# SBH_Charger_USB_PD.net
KiCad netlist of a schematic drawn in Altium Designer
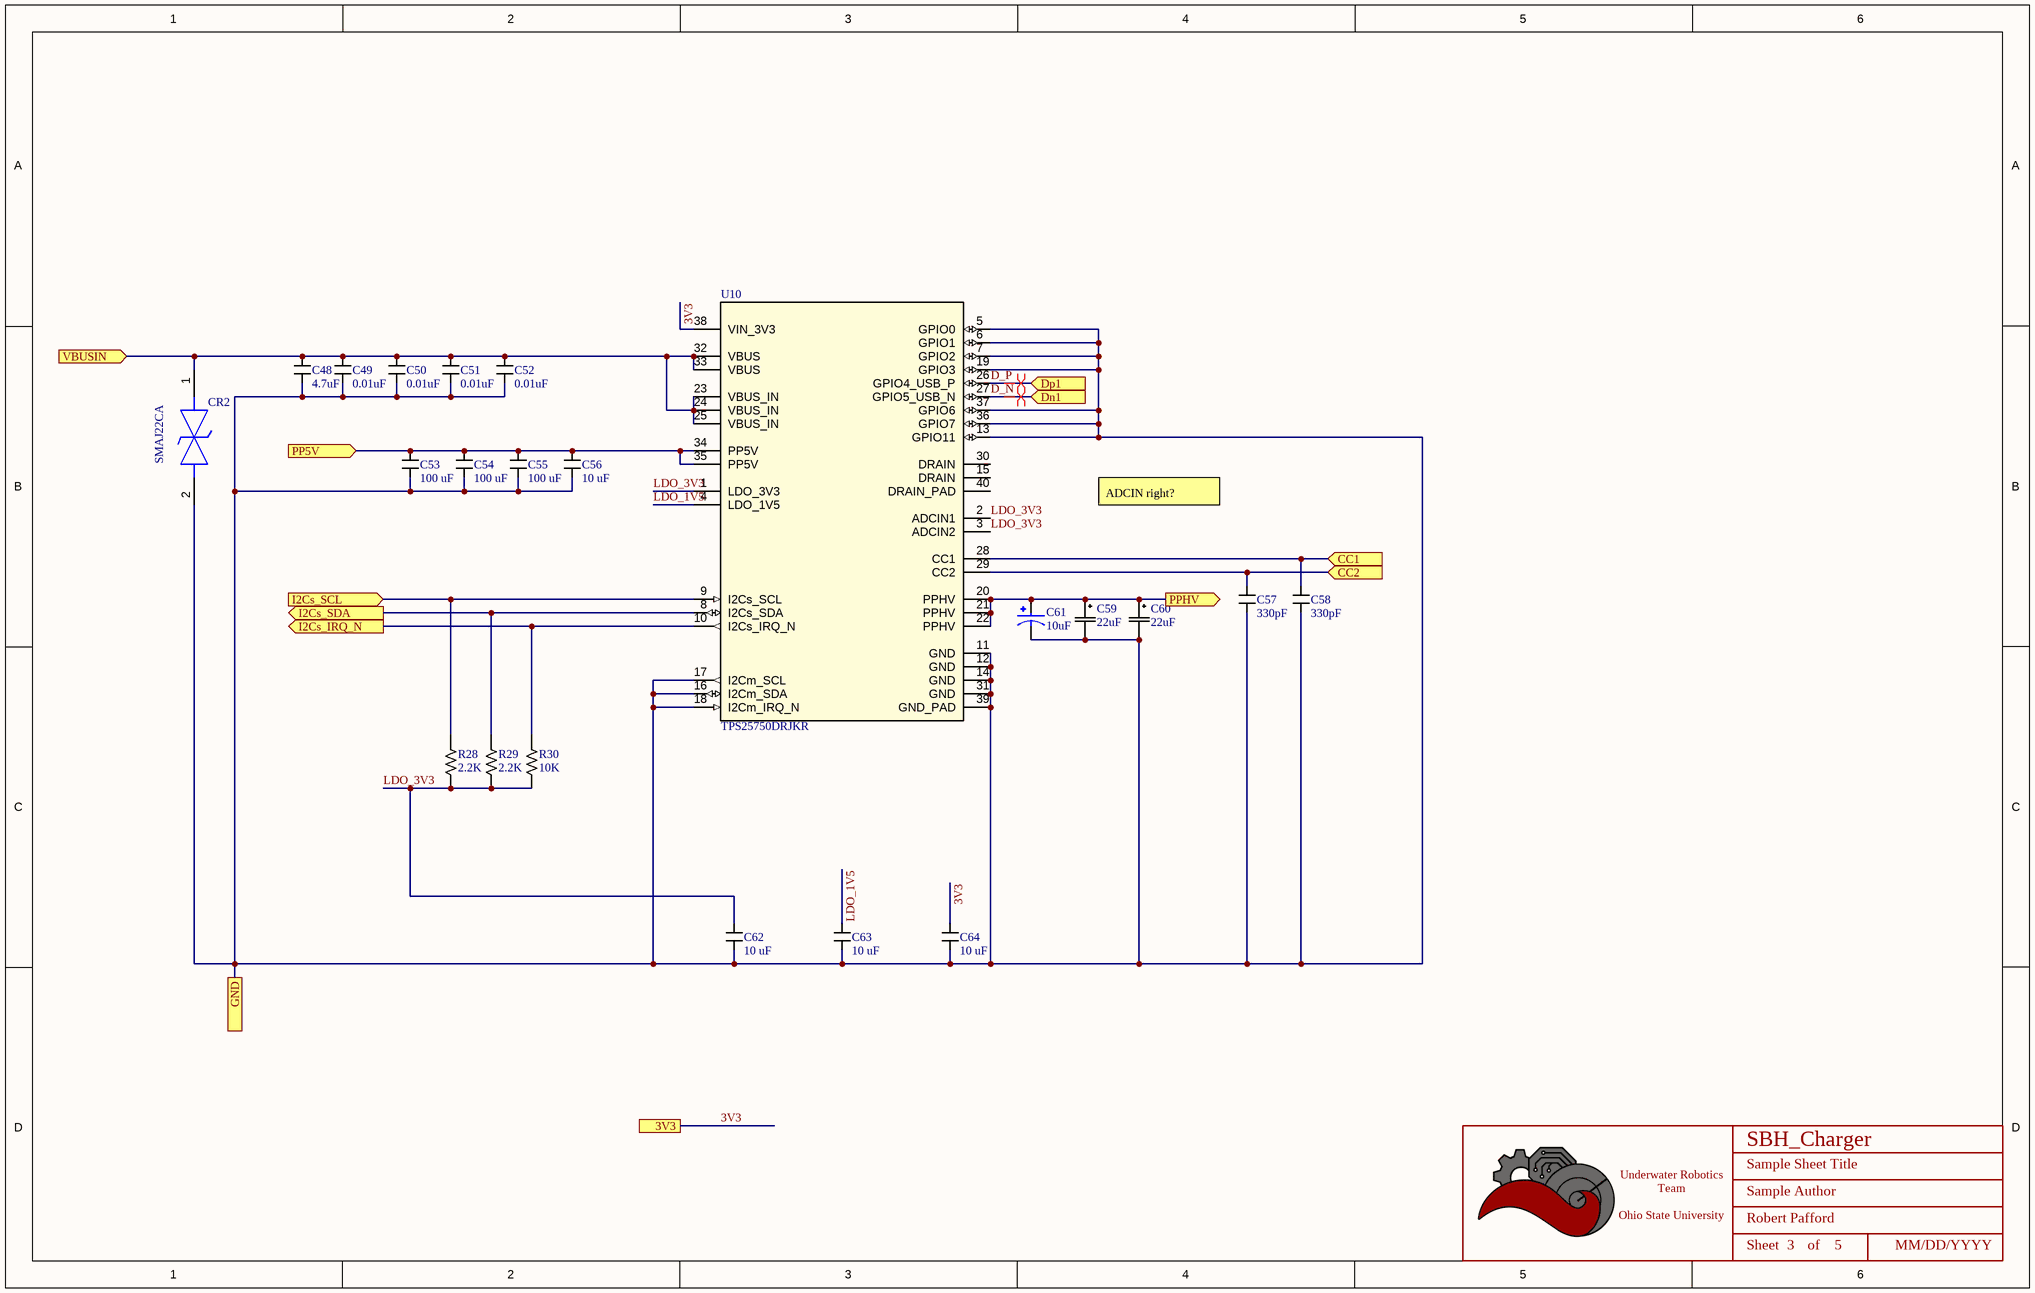
[diagram p0: SBH_Charger_USB_PD.SchDoc]

(export (version "E")
  (design (tool "Eeschema 10.0.6"))
  (components
    (comp (ref "C48")
      (value "4.7uF")
      (footprint "CAPACITOR_0603")
      (description "Cap 4.7uF 6.3V +/-10%\r\nCeramic 0603")
      (fields
        (field (name "TOLERANCE") "+/- 10%")
        (field (name "VOLTAGE") "6.3V")
        (field (name "MADE BY") "Robert Pafford")
      )
      (libsource (lib "Capacitors") (part "CAPACITOR_4.7uF_0603"))
    )
    (comp (ref "C49")
      (value "0.01uF")
      (footprint "CAPACITOR_0603")
      (description "Cap 10nF 6.3V +/-20%\r\nCeramic 0603")
      (fields
        (field (name "TOLERANCE") "+/- 10%")
        (field (name "VOLTAGE") "6.3V")
        (field (name "MADE BY") "Flip B")
      )
      (libsource (lib "Capacitors") (part "CAPACITOR_0.01uF_0603"))
    )
    (comp (ref "C50")
      (value "0.01uF")
      (footprint "CAPACITOR_0603")
      (description "Cap 10nF 6.3V +/-20%\r\nCeramic 0603")
      (fields
        (field (name "TOLERANCE") "+/- 10%")
        (field (name "VOLTAGE") "6.3V")
        (field (name "MADE BY") "Flip B")
      )
      (libsource (lib "Capacitors") (part "CAPACITOR_0.01uF_0603"))
    )
    (comp (ref "C51")
      (value "0.01uF")
      (footprint "CAPACITOR_0603")
      (description "Cap 10nF 6.3V +/-20%\r\nCeramic 0603")
      (fields
        (field (name "TOLERANCE") "+/- 10%")
        (field (name "VOLTAGE") "6.3V")
        (field (name "MADE BY") "Flip B")
      )
      (libsource (lib "Capacitors") (part "CAPACITOR_0.01uF_0603"))
    )
    (comp (ref "C52")
      (value "0.01uF")
      (footprint "CAPACITOR_0603")
      (description "Cap 10nF 6.3V +/-20%\r\nCeramic 0603")
      (fields
        (field (name "TOLERANCE") "+/- 10%")
        (field (name "VOLTAGE") "6.3V")
        (field (name "MADE BY") "Flip B")
      )
      (libsource (lib "Capacitors") (part "CAPACITOR_0.01uF_0603"))
    )
    (comp (ref "C53")
      (value "100uF Ceramic 6.3V")
      (footprint "CAPACITOR_0603")
      (description "Cap 100uF 6.3V +/-20%\r\nCeramic 0603")
      (fields
        (field (name "TOLERANCE") "+/- 20%")
        (field (name "VOLTAGE") "6.3V")
        (field (name "VALUE (UF)") "100 uF")
        (field (name "MADE BY") "Dylan Trainor")
      )
      (libsource (lib "Capacitors") (part "CAPACITOR_100uF_0603"))
    )
    (comp (ref "C54")
      (value "100uF Ceramic 6.3V")
      (footprint "CAPACITOR_0603")
      (description "Cap 100uF 6.3V +/-20%\r\nCeramic 0603")
      (fields
        (field (name "TOLERANCE") "+/- 20%")
        (field (name "VOLTAGE") "6.3V")
        (field (name "VALUE (UF)") "100 uF")
        (field (name "MADE BY") "Dylan Trainor")
      )
      (libsource (lib "Capacitors") (part "CAPACITOR_100uF_0603"))
    )
    (comp (ref "C55")
      (value "100uF Ceramic 6.3V")
      (footprint "CAPACITOR_0603")
      (description "Cap 100uF 6.3V +/-20%\r\nCeramic 0603")
      (fields
        (field (name "TOLERANCE") "+/- 20%")
        (field (name "VOLTAGE") "6.3V")
        (field (name "VALUE (UF)") "100 uF")
        (field (name "MADE BY") "Dylan Trainor")
      )
      (libsource (lib "Capacitors") (part "CAPACITOR_100uF_0603"))
    )
    (comp (ref "C56")
      (value "10uF Ceramic 6.3V")
      (footprint "CAPACITOR_0603")
      (description "Cap 10uF 6.3V +/-20%\r\nCeramic 0603")
      (fields
        (field (name "TOLERANCE") "+/- 20%")
        (field (name "VOLTAGE") "6.3V")
        (field (name "VALUE (UF)") "10 uF")
        (field (name "MADE BY") "Flip B")
      )
      (libsource (lib "Capacitors") (part "CAPACITOR_10uF_0603"))
    )
    (comp (ref "C57")
      (value "330pF")
      (footprint "CAPACITOR_0603")
      (description "Cap 330pF 16V +/-5%\r\nCeramic 0603")
      (fields
        (field (name "TOLERANCE") "+/- 5%")
        (field (name "VOLTAGE") "16V")
        (field (name "MADE BY") "Flip B")
      )
      (libsource (lib "Capacitors") (part "CAPACITOR_0.00033uF_0603"))
    )
    (comp (ref "C58")
      (value "330pF")
      (footprint "CAPACITOR_0603")
      (description "Cap 330pF 16V +/-5%\r\nCeramic 0603")
      (fields
        (field (name "TOLERANCE") "+/- 5%")
        (field (name "VOLTAGE") "16V")
        (field (name "MADE BY") "Flip B")
      )
      (libsource (lib "Capacitors") (part "CAPACITOR_0.00033uF_0603"))
    )
    (comp (ref "C59")
      (value "22uF")
      (footprint "PCAP_8x5.4-ELECT_NCA")
      (description "22 µF 35 V Aluminum Electrolytic Capacitors Radial, Can - SMD 1000 Hrs")
      (fields
        (field (name "VOLTAGE") "35V")
        (field (name "Comment") "22uF electrolytic 35 V")
        (field (name "MADE BY") "Robert Pafford")
      )
      (libsource (lib "Capacitors") (part "CAP ALUM 22UF 20% 35V SMD"))
    )
    (comp (ref "C60")
      (value "22uF")
      (footprint "PCAP_8x5.4-ELECT_NCA")
      (description "22 µF 35 V Aluminum Electrolytic Capacitors Radial, Can - SMD 1000 Hrs")
      (fields
        (field (name "VOLTAGE") "35V")
        (field (name "Comment") "22uF electrolytic 35 V")
        (field (name "MADE BY") "Robert Pafford")
      )
      (libsource (lib "Capacitors") (part "CAP ALUM 22UF 20% 35V SMD"))
    )
    (comp (ref "C61")
      (value "10uF")
      (footprint "CAP_EEHZC1J100P")
      (description "10 µF 63 V Aluminum - Polymer Capacitors Radial, Can SMD 120mOhm")
      (fields
        (field (name "TOLERANCE") "+/- 20%")
        (field (name "Comment") "10uF electrolytic 63V")
        (field (name "MADE BY") "Robert Pafford")
      )
      (libsource (lib "Capacitors") (part "CAP ALUM 10UF 20% 63V SMD"))
    )
    (comp (ref "C62")
      (value "10uF Ceramic 6.3V")
      (footprint "CAPACITOR_0603")
      (description "Cap 10uF 6.3V +/-20%\r\nCeramic 0603")
      (fields
        (field (name "TOLERANCE") "+/- 20%")
        (field (name "VOLTAGE") "6.3V")
        (field (name "VALUE (UF)") "10 uF")
        (field (name "MADE BY") "Flip B")
      )
      (libsource (lib "Capacitors") (part "CAPACITOR_10uF_0603"))
    )
    (comp (ref "C63")
      (value "10uF Ceramic 6.3V")
      (footprint "CAPACITOR_0603")
      (description "Cap 10uF 6.3V +/-20%\r\nCeramic 0603")
      (fields
        (field (name "TOLERANCE") "+/- 20%")
        (field (name "VOLTAGE") "6.3V")
        (field (name "VALUE (UF)") "10 uF")
        (field (name "MADE BY") "Flip B")
      )
      (libsource (lib "Capacitors") (part "CAPACITOR_10uF_0603"))
    )
    (comp (ref "C64")
      (value "10uF Ceramic 6.3V")
      (footprint "CAPACITOR_0603")
      (description "Cap 10uF 6.3V +/-20%\r\nCeramic 0603")
      (fields
        (field (name "TOLERANCE") "+/- 20%")
        (field (name "VOLTAGE") "6.3V")
        (field (name "VALUE (UF)") "10 uF")
        (field (name "MADE BY") "Flip B")
      )
      (libsource (lib "Capacitors") (part "CAPACITOR_10uF_0603"))
    )
    (comp (ref "CR2")
      (value "SMAJ22CA")
      (footprint "FP-SMAJ-CA-MFG")
      (description "TVS DIODE 22V 35.5V DO214AC")
      (libsource (lib "Altium Content Vault") (part "32812f50d15427265c9d073456c674c"))
    )
    (comp (ref "R28")
      (value "2.2k Ohm 1% 1/16W")
      (footprint "RESISTOR_0402")
      (description "RES 2.2K OHM 1% 1/16W 0402")
      (fields
        (field (name "TOLERANCE") "+/- 1%")
        (field (name "VALUE  (OHMS)") "2.2K")
        (field (name "MADE BY") "Megan McCabe")
      )
      (libsource (lib "Resistors") (part "RESISTOR_2.2K_0402_1"))
    )
    (comp (ref "R29")
      (value "2.2k Ohm 1% 1/16W")
      (footprint "RESISTOR_0402")
      (description "RES 2.2K OHM 1% 1/16W 0402")
      (fields
        (field (name "TOLERANCE") "+/- 1%")
        (field (name "VALUE  (OHMS)") "2.2K")
        (field (name "MADE BY") "Megan McCabe")
      )
      (libsource (lib "Resistors") (part "RESISTOR_2.2K_0402_1"))
    )
    (comp (ref "R30")
      (value "10k Ohm 1% 1/16W")
      (footprint "RESISTOR_0402")
      (description "RES 10k OHM 1% 1/16W 0402")
      (fields
        (field (name "TOLERANCE") "+/- 1%")
        (field (name "VALUE  (OHMS)") "10K")
        (field (name "MADE BY") "Robert Pafford")
      )
      (libsource (lib "Resistors") (part "RESISTOR_10K_0402"))
    )
    (comp (ref "U10")
      (value "TPS25750DRJKR")
      (footprint "38-WQFN (4x6)")
      (description "USB, Type-C Controller PMIC 38-WQFN (4x6)")
      (fields
        (field (name "COPYRIGHT") "Copyright (C) 2023 Ultra Librarian. All rights reserved.")
        (field (name "MADE BY") "Andrew Lin")
      )
      (libsource (lib "Integrated Circuits") (part "TPS25750DRJKR"))
    )
  )
  (nets
    (net (code "1") (name "/3V3") (class "Default")
      (node (ref "C64") (pin "1") (pinfunction "1_1") (pintype "passive"))
      (node (ref "U10") (pin "38") (pinfunction "VIN_3V3_38") (pintype "power_in"))
    )
    (net (code "2") (name "/CC1") (class "Default")
      (node (ref "C58") (pin "1") (pinfunction "1_1") (pintype "passive"))
      (node (ref "U10") (pin "28") (pinfunction "CC1_28") (pintype "passive"))
    )
    (net (code "3") (name "/CC2") (class "Default")
      (node (ref "C57") (pin "1") (pinfunction "1_1") (pintype "passive"))
      (node (ref "U10") (pin "29") (pinfunction "CC2_29") (pintype "passive"))
    )
    (net (code "4") (name "/D_N") (class "Default")
      (node (ref "U10") (pin "27") (pinfunction "GPIO5_USB_N_27") (pintype "bidirectional"))
    )
    (net (code "5") (name "/D_P") (class "Default")
      (node (ref "U10") (pin "26") (pinfunction "GPIO4_USB_P_26") (pintype "bidirectional"))
    )
    (net (code "6") (name "/GND") (class "Default")
      (node (ref "C48") (pin "2") (pinfunction "2_2") (pintype "passive"))
      (node (ref "C49") (pin "2") (pinfunction "2_2") (pintype "passive"))
      (node (ref "C50") (pin "2") (pinfunction "2_2") (pintype "passive"))
      (node (ref "C51") (pin "2") (pinfunction "2_2") (pintype "passive"))
      (node (ref "C52") (pin "2") (pinfunction "2_2") (pintype "passive"))
      (node (ref "C53") (pin "2") (pinfunction "2_2") (pintype "passive"))
      (node (ref "C54") (pin "2") (pinfunction "2_2") (pintype "passive"))
      (node (ref "C55") (pin "2") (pinfunction "2_2") (pintype "passive"))
      (node (ref "C56") (pin "2") (pinfunction "2_2") (pintype "passive"))
      (node (ref "C57") (pin "2") (pinfunction "2_2") (pintype "passive"))
      (node (ref "C58") (pin "2") (pinfunction "2_2") (pintype "passive"))
      (node (ref "C59") (pin "2") (pinfunction "2_2") (pintype "passive"))
      (node (ref "C60") (pin "2") (pinfunction "2_2") (pintype "passive"))
      (node (ref "C61") (pin "2") (pinfunction "2_2") (pintype "passive"))
      (node (ref "C62") (pin "2") (pinfunction "2_2") (pintype "passive"))
      (node (ref "C63") (pin "2") (pinfunction "2_2") (pintype "passive"))
      (node (ref "C64") (pin "2") (pinfunction "2_2") (pintype "passive"))
      (node (ref "CR2") (pin "2") (pinfunction "2_2") (pintype "passive"))
      (node (ref "U10") (pin "11") (pinfunction "GND_11") (pintype "power_in"))
      (node (ref "U10") (pin "12") (pinfunction "GND_12") (pintype "power_in"))
      (node (ref "U10") (pin "13") (pinfunction "GPIO11_13") (pintype "bidirectional"))
      (node (ref "U10") (pin "14") (pinfunction "GND_14") (pintype "power_in"))
      (node (ref "U10") (pin "16") (pinfunction "I2Cm_SDA_16") (pintype "bidirectional"))
      (node (ref "U10") (pin "17") (pinfunction "I2Cm_SCL_17") (pintype "output"))
      (node (ref "U10") (pin "18") (pinfunction "I2Cm_IRQ_N_18") (pintype "input"))
      (node (ref "U10") (pin "19") (pinfunction "GPIO3_19") (pintype "bidirectional"))
      (node (ref "U10") (pin "31") (pinfunction "GND_31") (pintype "power_in"))
      (node (ref "U10") (pin "36") (pinfunction "GPIO7_36") (pintype "bidirectional"))
      (node (ref "U10") (pin "37") (pinfunction "GPIO6_37") (pintype "bidirectional"))
      (node (ref "U10") (pin "39") (pinfunction "GND_PAD_39") (pintype "power_in"))
      (node (ref "U10") (pin "5") (pinfunction "GPIO0_5") (pintype "bidirectional"))
      (node (ref "U10") (pin "6") (pinfunction "GPIO1_6") (pintype "bidirectional"))
      (node (ref "U10") (pin "7") (pinfunction "GPIO2_7") (pintype "bidirectional"))
    )
    (net (code "7") (name "/I2Cs_IRQ_N") (class "Default")
      (node (ref "R30") (pin "1") (pinfunction "1_1") (pintype "passive"))
      (node (ref "U10") (pin "10") (pinfunction "I2Cs_IRQ_N_10") (pintype "output"))
    )
    (net (code "8") (name "/I2Cs_SCL") (class "Default")
      (node (ref "R28") (pin "1") (pinfunction "1_1") (pintype "passive"))
      (node (ref "U10") (pin "9") (pinfunction "I2Cs_SCL_9") (pintype "input"))
    )
    (net (code "9") (name "/I2Cs_SDA") (class "Default")
      (node (ref "R29") (pin "1") (pinfunction "1_1") (pintype "passive"))
      (node (ref "U10") (pin "8") (pinfunction "I2Cs_SDA_8") (pintype "bidirectional"))
    )
    (net (code "10") (name "/LDO_1V5") (class "Default")
      (node (ref "C63") (pin "1") (pinfunction "1_1") (pintype "passive"))
      (node (ref "U10") (pin "4") (pinfunction "LDO_1V5_4") (pintype "passive"))
    )
    (net (code "11") (name "/LDO_3V3") (class "Default")
      (node (ref "C62") (pin "1") (pinfunction "1_1") (pintype "passive"))
      (node (ref "R28") (pin "2") (pinfunction "2_2") (pintype "passive"))
      (node (ref "R29") (pin "2") (pinfunction "2_2") (pintype "passive"))
      (node (ref "R30") (pin "2") (pinfunction "2_2") (pintype "passive"))
      (node (ref "U10") (pin "1") (pinfunction "LDO_3V3_1") (pintype "passive"))
      (node (ref "U10") (pin "2") (pinfunction "ADCIN1_2") (pintype "passive"))
      (node (ref "U10") (pin "3") (pinfunction "ADCIN2_3") (pintype "passive"))
    )
    (net (code "12") (name "/PP5V") (class "Default")
      (node (ref "C53") (pin "1") (pinfunction "1_1") (pintype "passive"))
      (node (ref "C54") (pin "1") (pinfunction "1_1") (pintype "passive"))
      (node (ref "C55") (pin "1") (pinfunction "1_1") (pintype "passive"))
      (node (ref "C56") (pin "1") (pinfunction "1_1") (pintype "passive"))
      (node (ref "U10") (pin "34") (pinfunction "PP5V_34") (pintype "power_in"))
      (node (ref "U10") (pin "35") (pinfunction "PP5V_35") (pintype "power_in"))
    )
    (net (code "13") (name "/PPHV") (class "Default")
      (node (ref "C59") (pin "1") (pinfunction "1_1") (pintype "passive"))
      (node (ref "C60") (pin "1") (pinfunction "1_1") (pintype "passive"))
      (node (ref "C61") (pin "1") (pinfunction "1_1") (pintype "passive"))
      (node (ref "U10") (pin "20") (pinfunction "PPHV_20") (pintype "passive"))
      (node (ref "U10") (pin "21") (pinfunction "PPHV_21") (pintype "passive"))
      (node (ref "U10") (pin "22") (pinfunction "PPHV_22") (pintype "passive"))
    )
    (net (code "14") (name "/VBUSIN") (class "Default")
      (node (ref "C48") (pin "1") (pinfunction "1_1") (pintype "passive"))
      (node (ref "C49") (pin "1") (pinfunction "1_1") (pintype "passive"))
      (node (ref "C50") (pin "1") (pinfunction "1_1") (pintype "passive"))
      (node (ref "C51") (pin "1") (pinfunction "1_1") (pintype "passive"))
      (node (ref "C52") (pin "1") (pinfunction "1_1") (pintype "passive"))
      (node (ref "CR2") (pin "1") (pinfunction "1_1") (pintype "passive"))
      (node (ref "U10") (pin "23") (pinfunction "VBUS_IN_23") (pintype "power_in"))
      (node (ref "U10") (pin "24") (pinfunction "VBUS_IN_24") (pintype "power_in"))
      (node (ref "U10") (pin "25") (pinfunction "VBUS_IN_25") (pintype "power_in"))
      (node (ref "U10") (pin "32") (pinfunction "VBUS_32") (pintype "power_in"))
      (node (ref "U10") (pin "33") (pinfunction "VBUS_33") (pintype "power_in"))
    )
    (net (code "15") (name "unconnected-(U10-DRAIN-Pad15)") (class "Default")
      (node (ref "U10") (pin "15") (pinfunction "DRAIN_15") (pintype "passive"))
    )
    (net (code "16") (name "unconnected-(U10-DRAIN-Pad30)") (class "Default")
      (node (ref "U10") (pin "30") (pinfunction "DRAIN_30") (pintype "passive"))
    )
    (net (code "17") (name "unconnected-(U10-DRAIN_PAD-Pad40)") (class "Default")
      (node (ref "U10") (pin "40") (pinfunction "DRAIN_PAD_40") (pintype "passive"))
    )
  )
)
